# zulu_a7_4.net
KiCad netlist of a schematic drawn in Altium Designer
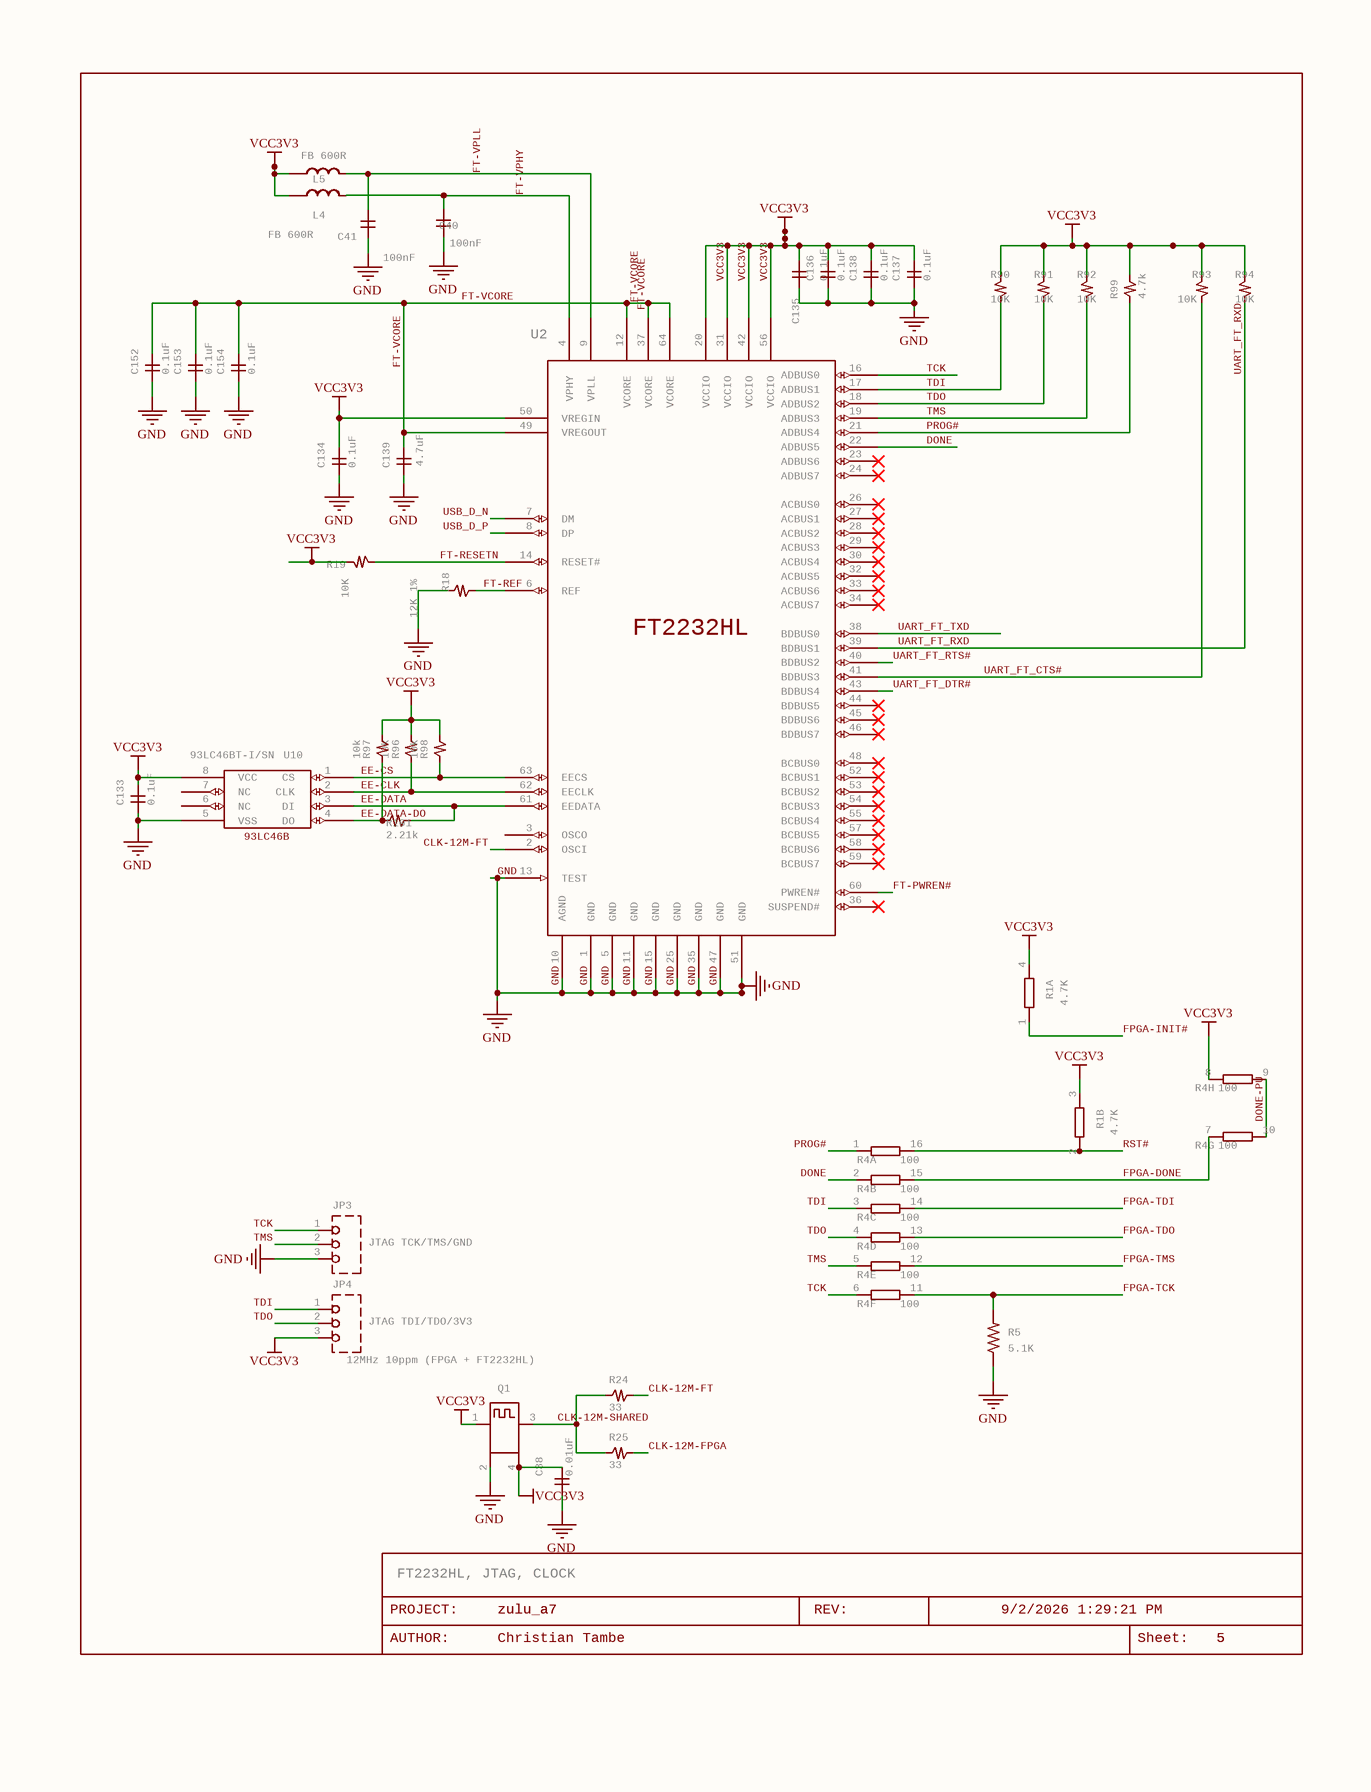
[diagram p0: zulu_a7_4.SchDoc]

(export (version "E")
  (design (tool "Eeschema 10.0.6"))
  (components
    (comp (ref "C38")
      (value "0.01uF")
      (footprint "C0201")
      (description "CAPACITOR, generic non-polarized, horizontal pins")
      (fields (field (name "MANF") "Murata"))
      (libsource (lib "rcl") (part "C-GENERICC0201"))
    )
    (comp (ref "C40")
      (value "100nF")
      (footprint "C0201")
      (description "CAPACITOR, generic non-polarized, horizontal pins")
      (fields (field (name "MANF") "Murata"))
      (libsource (lib "rcl") (part "C-GENERICC0201"))
    )
    (comp (ref "C41")
      (value "100nF")
      (footprint "C0201")
      (description "CAPACITOR, generic non-polarized, horizontal pins")
      (fields (field (name "MANF") "Murata"))
      (libsource (lib "") (part "C-GENERICC0201_2"))
    )
    (comp (ref "C133")
      (value "0.1uF")
      (footprint "C0201")
      (description "CAPACITOR, generic non-polarized, horizontal pins")
      (fields (field (name "MANF") "Murata"))
      (libsource (lib "rcl") (part "C-GENERICC0201"))
    )
    (comp (ref "C134")
      (value "0.1uF")
      (footprint "C0201")
      (description "CAPACITOR, generic non-polarized, horizontal pins")
      (fields (field (name "MANF") "Murata"))
      (libsource (lib "rcl") (part "C-GENERICC0201"))
    )
    (comp (ref "C135")
      (value "0.1uF")
      (footprint "C0201")
      (description "CAPACITOR, generic non-polarized, horizontal pins")
      (fields (field (name "MANF") "Murata"))
      (libsource (lib "rcl") (part "C-GENERICC0201"))
    )
    (comp (ref "C136")
      (value "0.1uF")
      (footprint "C0201")
      (description "CAPACITOR, generic non-polarized, horizontal pins")
      (fields (field (name "MANF") "Murata"))
      (libsource (lib "rcl") (part "C-GENERICC0201"))
    )
    (comp (ref "C137")
      (value "0.1uF")
      (footprint "C0201")
      (description "CAPACITOR, generic non-polarized, horizontal pins")
      (fields (field (name "MANF") "Murata"))
      (libsource (lib "rcl") (part "C-GENERICC0201"))
    )
    (comp (ref "C138")
      (value "0.1uF")
      (footprint "C0201")
      (description "CAPACITOR, generic non-polarized, horizontal pins")
      (fields (field (name "MANF") "Murata"))
      (libsource (lib "rcl") (part "C-GENERICC0201"))
    )
    (comp (ref "C139")
      (value "4.7uF")
      (footprint "C0402")
      (description "CAPACITOR, generic non-polarized, horizontal pins")
      (fields (field (name "MANF") "Taiyo Yuden"))
      (libsource (lib "rcl") (part "C-GENERICC0402"))
    )
    (comp (ref "C152")
      (value "0.1uF")
      (footprint "C0201")
      (description "CAPACITOR, generic non-polarized, horizontal pins")
      (fields (field (name "MANF") "Murata"))
      (libsource (lib "") (part "C-GENERICC0201_1"))
    )
    (comp (ref "C153")
      (value "0.1uF")
      (footprint "C0201")
      (description "CAPACITOR, generic non-polarized, horizontal pins")
      (fields (field (name "MANF") "Murata"))
      (libsource (lib "") (part "C-GENERICC0201_1"))
    )
    (comp (ref "C154")
      (value "0.1uF")
      (footprint "C0201")
      (description "CAPACITOR, generic non-polarized, horizontal pins")
      (fields (field (name "MANF") "Murata"))
      (libsource (lib "") (part "C-GENERICC0201_1"))
    )
    (comp (ref "FRAME4")
      (value "DOCFIELD")
      (description "DOCUMENT FIELD")
      (fields
        (field (name "LAST_DATE_TIME") "9/2/2026 1:29:21 PM")
        (field (name "SHEET") "Sheet:")
        (field (name "SHEET_1") "5")
        (field (name "REV") "REV:")
        (field (name "PROJECT") "PROJECT:")
        (field (name "DRAWING_NAME") "zulu_a7")
        (field (name "AUTHOR") "Christian Tambe")
        (field (name "DRAWING_NAME_1") "zulu_a7")
        (field (name "SHEET_2") "5")
        (field (name "LIBRARYNAME") "ctambe")
      )
      (libsource (lib "ctambe") (part "DOCFIELD"))
    )
    (comp (ref "JP3")
      (value "JTAG TCK/TMS/GND")
      (footprint "1X03-NOSILK")
      (fields (field (name "LIBRARYNAME") "pinhead"))
      (libsource (lib "pinhead") (part "TESTPT-1X3NOSILK"))
    )
    (comp (ref "JP4")
      (value "JTAG TDI/TDO/3V3")
      (footprint "1X03-NOSILK")
      (fields (field (name "LIBRARYNAME") "pinhead"))
      (libsource (lib "pinhead") (part "TESTPT-1X3NOSILK"))
    )
    (comp (ref "L4")
      (value "FB 600R")
      (footprint "IND0603")
      (description "INDUCTOR, generic power inductor")
      (fields (field (name "MANF") "Murata") (field (name "LIBRARYNAME") "ctambe"))
      (libsource (lib "ctambe") (part "INDUCTOR"))
    )
    (comp (ref "L5")
      (value "FB 600R")
      (footprint "IND0603")
      (description "INDUCTOR, generic power inductor")
      (fields (field (name "MANF") "Murata") (field (name "LIBRARYNAME") "ctambe"))
      (libsource (lib "ctambe") (part "INDUCTOR"))
    )
    (comp (ref "Q1")
      (value "12MHz 10ppm (FPGA + FT2232HL)")
      (footprint "32X25")
      (description "Crystal Chip")
      (fields (field (name "MANF") "ECS") (field (name "LIBRARYNAME") "ctambe"))
      (libsource (lib "ctambe") (part "OSC_CHIPASEM1-12MHZ"))
    )
    (comp (ref "R1")
      (value "4.7K")
      (footprint "742C043")
      (description "Resistor 2-pack   Package of two resistors.")
      (fields (field (name "MANF") "CTS") (field (name "LIBRARYNAME") "ctambe"))
      (libsource (lib "") (part "RES2742_1"))
    )
    (comp (ref "R4")
      (value "100")
      (footprint "742C163")
      (description "Resistor 8-pack   Package of eight resistors, six used.")
      (fields (field (name "MANF") "CTS") (field (name "LIBRARYNAME") "ctambe"))
      (libsource (lib "ctambe") (part "RES8742"))
    )
    (comp (ref "R5")
      (value "5.1K")
      (footprint "R0201")
      (description "RESISTOR, American symbol")
      (fields (field (name "MANF") "Yageo"))
      (libsource (lib "rcl") (part "R-US_R0201"))
    )
    (comp (ref "R18")
      (value "12K 1%")
      (footprint "R0402")
      (description "RESISTOR, American symbol, small 2-zigzag variant (sheet 2 only)")
      (fields (field (name "MANF") "Yageo"))
      (libsource (lib "rcl") (part "R-US_SMALLR0402"))
    )
    (comp (ref "R19")
      (value "10K")
      (footprint "R0201")
      (description "RESISTOR, American symbol, small 2-zigzag variant (sheet 2 only)")
      (fields (field (name "MANF") "Yageo"))
      (libsource (lib "rcl") (part "R-US_SMALLR0201"))
    )
    (comp (ref "R24")
      (value "33")
      (footprint "R0201")
      (description "RESISTOR, American symbol, small 2-zigzag variant (sheet 2 only)")
      (fields (field (name "MANF") "Yageo"))
      (libsource (lib "rcl") (part "R-US_SMALLR0201"))
    )
    (comp (ref "R25")
      (value "33")
      (footprint "R0201")
      (description "RESISTOR, American symbol, small 2-zigzag variant (sheet 2 only)")
      (fields (field (name "MANF") "Yageo"))
      (libsource (lib "rcl") (part "R-US_SMALLR0201"))
    )
    (comp (ref "R90")
      (value "10K")
      (footprint "R0201")
      (description "RESISTOR, American symbol, small 2-zigzag variant (sheet 2 only)")
      (fields (field (name "MANF") "Yageo"))
      (libsource (lib "rcl") (part "R-US_SMALLR0201"))
    )
    (comp (ref "R91")
      (value "10K")
      (footprint "R0201")
      (description "RESISTOR, American symbol, small 2-zigzag variant (sheet 2 only)")
      (fields (field (name "MANF") "Yageo"))
      (libsource (lib "rcl") (part "R-US_SMALLR0201"))
    )
    (comp (ref "R92")
      (value "10K")
      (footprint "R0201")
      (description "RESISTOR, American symbol, small 2-zigzag variant (sheet 2 only)")
      (fields (field (name "MANF") "Yageo"))
      (libsource (lib "rcl") (part "R-US_SMALLR0201"))
    )
    (comp (ref "R93")
      (value "10K")
      (footprint "R0201")
      (description "RESISTOR, American symbol, small 2-zigzag variant (sheet 2 only)")
      (fields (field (name "MANF") "Yageo"))
      (libsource (lib "rcl") (part "R-US_SMALLR0201"))
    )
    (comp (ref "R94")
      (value "10K")
      (footprint "R0201")
      (description "RESISTOR, American symbol, small 2-zigzag variant (sheet 2 only)")
      (fields (field (name "MANF") "Yageo"))
      (libsource (lib "rcl") (part "R-US_SMALLR0201"))
    )
    (comp (ref "R96")
      (value "10k")
      (footprint "R0201")
      (description "RESISTOR, American symbol, small 2-zigzag variant (sheet 2 only)")
      (fields (field (name "MANF") "Yageo"))
      (libsource (lib "rcl") (part "R-US_SMALLR0201"))
    )
    (comp (ref "R97")
      (value "10k")
      (footprint "R0201")
      (description "RESISTOR, American symbol, small 2-zigzag variant (sheet 2 only)")
      (fields (field (name "MANF") "Yageo"))
      (libsource (lib "rcl") (part "R-US_SMALLR0201"))
    )
    (comp (ref "R98")
      (value "10k")
      (footprint "R0201")
      (description "RESISTOR, American symbol, small 2-zigzag variant (sheet 2 only)")
      (fields (field (name "MANF") "Yageo"))
      (libsource (lib "rcl") (part "R-US_SMALLR0201"))
    )
    (comp (ref "R99")
      (value "4.7k")
      (footprint "R0201")
      (description "RESISTOR, American symbol, small 2-zigzag variant (sheet 2 only)")
      (fields (field (name "MANF") "Yageo"))
      (libsource (lib "rcl") (part "R-US_SMALLR0201"))
    )
    (comp (ref "R101")
      (value "2.21k")
      (footprint "R0201")
      (description "RESISTOR, American symbol, small 2-zigzag variant (sheet 2 only)")
      (fields (field (name "MANF") "Yageo"))
      (libsource (lib "rcl") (part "R-US_SMALLR0201"))
    )
    (comp (ref "U2")
      (value "FT2232HL USB-UART/JTAG Bridge")
      (footprint "FT2232HL-LQFP64")
      (fields
        (field (name "FT2232HL") "FT2232HL")
        (field (name "MANF") "FTDI")
        (field (name "LIBRARYNAME") "ctambe")
      )
      (libsource (lib "ctambe") (part "FT2232HL-LQFP64"))
    )
    (comp (ref "U10")
      (value "93LC46BT-I/SN")
      (footprint "SPI-8_SOIC_150")
      (fields
        (field (name "93LC46B") "93LC46B")
        (field (name "MANF") "Microchip")
        (field (name "LIBRARYNAME") "ctambe")
      )
      (libsource (lib "ctambe") (part "EEPROM-93LC46B-I/SN"))
    )
  )
  (nets
    (net (code "1") (name "/CLK-12M-FPGA") (class "Default")
      (node (ref "R25") (pin "2") (pinfunction "2_2") (pintype "passive"))
    )
    (net (code "2") (name "/CLK-12M-FT") (class "Default")
      (node (ref "R24") (pin "2") (pinfunction "2_2") (pintype "passive"))
      (node (ref "U2") (pin "2") (pinfunction "OSCI_2") (pintype "bidirectional"))
    )
    (net (code "3") (name "/CLK-12M-SHARED") (class "Default")
      (node (ref "Q1") (pin "3") (pinfunction "3_3") (pintype "passive"))
      (node (ref "R24") (pin "1") (pinfunction "1_1") (pintype "passive"))
      (node (ref "R25") (pin "1") (pinfunction "1_1") (pintype "passive"))
    )
    (net (code "4") (name "/DONE") (class "Default")
      (node (ref "R4") (pin "2") (pinfunction "1_2") (pintype "passive"))
      (node (ref "U2") (pin "22") (pinfunction "ADBUS5_22") (pintype "bidirectional"))
    )
    (net (code "5") (name "/DONE-PU") (class "Default")
      (node (ref "R4") (pin "10") (pinfunction "2_10") (pintype "passive"))
      (node (ref "R4") (pin "9") (pinfunction "2_9") (pintype "passive"))
    )
    (net (code "6") (name "/EE-CLK") (class "Default")
      (node (ref "R96") (pin "1") (pinfunction "1_1") (pintype "passive"))
      (node (ref "U10") (pin "2") (pinfunction "CLK_2") (pintype "bidirectional"))
      (node (ref "U2") (pin "62") (pinfunction "EECLK_62") (pintype "bidirectional"))
    )
    (net (code "7") (name "/EE-CS") (class "Default")
      (node (ref "R98") (pin "1") (pinfunction "1_1") (pintype "passive"))
      (node (ref "U10") (pin "1") (pinfunction "CS_1") (pintype "bidirectional"))
      (node (ref "U2") (pin "63") (pinfunction "EECS_63") (pintype "bidirectional"))
    )
    (net (code "8") (name "/EE-DATA") (class "Default")
      (node (ref "R101") (pin "2") (pinfunction "2_2") (pintype "passive"))
      (node (ref "U10") (pin "3") (pinfunction "DI_3") (pintype "bidirectional"))
      (node (ref "U2") (pin "61") (pinfunction "EEDATA_61") (pintype "bidirectional"))
    )
    (net (code "9") (name "/EE-DATA-DO") (class "Default")
      (node (ref "R101") (pin "1") (pinfunction "1_1") (pintype "passive"))
      (node (ref "R97") (pin "1") (pinfunction "1_1") (pintype "passive"))
      (node (ref "U10") (pin "4") (pinfunction "DO_4") (pintype "bidirectional"))
    )
    (net (code "10") (name "/FPGA-DONE") (class "Default")
      (node (ref "R4") (pin "15") (pinfunction "2_15") (pintype "passive"))
      (node (ref "R4") (pin "7") (pinfunction "1_7") (pintype "passive"))
    )
    (net (code "11") (name "/FPGA-INIT#") (class "Default")
      (node (ref "R1") (pin "1") (pinfunction "1_1") (pintype "passive"))
    )
    (net (code "12") (name "/FPGA-TCK") (class "Default")
      (node (ref "R4") (pin "11") (pinfunction "2_11") (pintype "passive"))
      (node (ref "R5") (pin "2") (pinfunction "2_2") (pintype "passive"))
    )
    (net (code "13") (name "/FPGA-TDI") (class "Default")
      (node (ref "R4") (pin "14") (pinfunction "2_14") (pintype "passive"))
    )
    (net (code "14") (name "/FPGA-TDO") (class "Default")
      (node (ref "R4") (pin "13") (pinfunction "2_13") (pintype "passive"))
    )
    (net (code "15") (name "/FPGA-TMS") (class "Default")
      (node (ref "R4") (pin "12") (pinfunction "2_12") (pintype "passive"))
    )
    (net (code "16") (name "/FT-PWREN#") (class "Default")
      (node (ref "U2") (pin "60") (pinfunction "PWREN#_60") (pintype "bidirectional"))
    )
    (net (code "17") (name "/FT-REF") (class "Default")
      (node (ref "R18") (pin "2") (pinfunction "2_2") (pintype "passive"))
      (node (ref "U2") (pin "6") (pinfunction "REF_6") (pintype "bidirectional"))
    )
    (net (code "18") (name "/FT-RESETN") (class "Default")
      (node (ref "R19") (pin "1") (pinfunction "1_1") (pintype "passive"))
      (node (ref "U2") (pin "14") (pinfunction "RESET#_14") (pintype "bidirectional"))
    )
    (net (code "19") (name "/FT-VCORE") (class "Default")
      (node (ref "C139") (pin "2") (pinfunction "2_2") (pintype "passive"))
      (node (ref "C152") (pin "2") (pinfunction "2_2") (pintype "passive"))
      (node (ref "C153") (pin "2") (pinfunction "2_2") (pintype "passive"))
      (node (ref "C154") (pin "2") (pinfunction "2_2") (pintype "passive"))
      (node (ref "U2") (pin "12") (pinfunction "VCORE_12") (pintype "power_in"))
      (node (ref "U2") (pin "37") (pinfunction "VCORE_37") (pintype "power_in"))
      (node (ref "U2") (pin "49") (pinfunction "VREGOUT_49") (pintype "power_in"))
      (node (ref "U2") (pin "64") (pinfunction "VCORE_64") (pintype "power_in"))
    )
    (net (code "20") (name "/FT-VPHY") (class "Default")
      (node (ref "C40") (pin "2") (pinfunction "2_2") (pintype "passive"))
      (node (ref "L4") (pin "1") (pinfunction "1_1") (pintype "passive"))
      (node (ref "U2") (pin "4") (pinfunction "VPHY_4") (pintype "power_in"))
    )
    (net (code "21") (name "/FT-VPLL") (class "Default")
      (node (ref "C41") (pin "2") (pinfunction "2_2") (pintype "passive"))
      (node (ref "L5") (pin "1") (pinfunction "1_1") (pintype "passive"))
      (node (ref "U2") (pin "9") (pinfunction "VPLL_9") (pintype "power_in"))
    )
    (net (code "22") (name "/PROG#") (class "Default")
      (node (ref "R4") (pin "1") (pinfunction "1_1") (pintype "passive"))
      (node (ref "R99") (pin "1") (pinfunction "1_1") (pintype "passive"))
      (node (ref "U2") (pin "21") (pinfunction "ADBUS4_21") (pintype "bidirectional"))
    )
    (net (code "23") (name "/RST#") (class "Default")
      (node (ref "R1") (pin "2") (pinfunction "1_2") (pintype "passive"))
      (node (ref "R4") (pin "16") (pinfunction "2_16") (pintype "passive"))
    )
    (net (code "24") (name "/TCK") (class "Default")
      (node (ref "JP3") (pin "1") (pinfunction "1_1") (pintype "passive"))
      (node (ref "R4") (pin "6") (pinfunction "1_6") (pintype "passive"))
      (node (ref "U2") (pin "16") (pinfunction "ADBUS0_16") (pintype "bidirectional"))
    )
    (net (code "25") (name "/TDI") (class "Default")
      (node (ref "JP4") (pin "1") (pinfunction "1_1") (pintype "passive"))
      (node (ref "R4") (pin "3") (pinfunction "1_3") (pintype "passive"))
      (node (ref "R90") (pin "1") (pinfunction "1_1") (pintype "passive"))
      (node (ref "U2") (pin "17") (pinfunction "ADBUS1_17") (pintype "bidirectional"))
    )
    (net (code "26") (name "/TDO") (class "Default")
      (node (ref "JP4") (pin "2") (pinfunction "2_2") (pintype "passive"))
      (node (ref "R4") (pin "4") (pinfunction "1_4") (pintype "passive"))
      (node (ref "R91") (pin "1") (pinfunction "1_1") (pintype "passive"))
      (node (ref "U2") (pin "18") (pinfunction "ADBUS2_18") (pintype "bidirectional"))
    )
    (net (code "27") (name "/TMS") (class "Default")
      (node (ref "JP3") (pin "2") (pinfunction "2_2") (pintype "passive"))
      (node (ref "R4") (pin "5") (pinfunction "1_5") (pintype "passive"))
      (node (ref "R92") (pin "1") (pinfunction "1_1") (pintype "passive"))
      (node (ref "U2") (pin "19") (pinfunction "ADBUS3_19") (pintype "bidirectional"))
    )
    (net (code "28") (name "/UART_FT_CTS#") (class "Default")
      (node (ref "R93") (pin "1") (pinfunction "1_1") (pintype "passive"))
      (node (ref "U2") (pin "41") (pinfunction "BDBUS3_41") (pintype "bidirectional"))
    )
    (net (code "29") (name "/UART_FT_DTR#") (class "Default")
      (node (ref "U2") (pin "43") (pinfunction "BDBUS4_43") (pintype "bidirectional"))
    )
    (net (code "30") (name "/UART_FT_RTS#") (class "Default")
      (node (ref "U2") (pin "40") (pinfunction "BDBUS2_40") (pintype "bidirectional"))
    )
    (net (code "31") (name "/UART_FT_RXD") (class "Default")
      (node (ref "R94") (pin "1") (pinfunction "1_1") (pintype "passive"))
      (node (ref "U2") (pin "39") (pinfunction "BDBUS1_39") (pintype "bidirectional"))
    )
    (net (code "32") (name "/UART_FT_TXD") (class "Default")
      (node (ref "U2") (pin "38") (pinfunction "BDBUS0_38") (pintype "bidirectional"))
    )
    (net (code "33") (name "/USB_D_N") (class "Default")
      (node (ref "U2") (pin "7") (pinfunction "DM_7") (pintype "bidirectional"))
    )
    (net (code "34") (name "/USB_D_P") (class "Default")
      (node (ref "U2") (pin "8") (pinfunction "DP_8") (pintype "bidirectional"))
    )
    (net (code "35") (name "GND") (class "Default")
      (node (ref "C133") (pin "1") (pinfunction "1_1") (pintype "passive"))
      (node (ref "C134") (pin "1") (pinfunction "1_1") (pintype "passive"))
      (node (ref "C135") (pin "1") (pinfunction "1_1") (pintype "passive"))
      (node (ref "C136") (pin "1") (pinfunction "1_1") (pintype "passive"))
      (node (ref "C137") (pin "1") (pinfunction "1_1") (pintype "passive"))
      (node (ref "C138") (pin "1") (pinfunction "1_1") (pintype "passive"))
      (node (ref "C139") (pin "1") (pinfunction "1_1") (pintype "passive"))
      (node (ref "C152") (pin "1") (pinfunction "1_1") (pintype "passive"))
      (node (ref "C153") (pin "1") (pinfunction "1_1") (pintype "passive"))
      (node (ref "C154") (pin "1") (pinfunction "1_1") (pintype "passive"))
      (node (ref "C38") (pin "1") (pinfunction "1_1") (pintype "passive"))
      (node (ref "C40") (pin "1") (pinfunction "1_1") (pintype "passive"))
      (node (ref "C41") (pin "1") (pinfunction "1_1") (pintype "passive"))
      (node (ref "JP3") (pin "3") (pinfunction "3_3") (pintype "passive"))
      (node (ref "Q1") (pin "2") (pinfunction "2_2") (pintype "passive"))
      (node (ref "R18") (pin "1") (pinfunction "1_1") (pintype "passive"))
      (node (ref "R5") (pin "1") (pinfunction "1_1") (pintype "passive"))
      (node (ref "U10") (pin "5") (pinfunction "VSS_5") (pintype "power_in"))
      (node (ref "U2") (pin "1") (pinfunction "GND_1") (pintype "power_in"))
      (node (ref "U2") (pin "10") (pinfunction "AGND_10") (pintype "power_in"))
      (node (ref "U2") (pin "11") (pinfunction "GND_11") (pintype "power_in"))
      (node (ref "U2") (pin "13") (pinfunction "TEST_13") (pintype "input"))
      (node (ref "U2") (pin "15") (pinfunction "GND_15") (pintype "power_in"))
      (node (ref "U2") (pin "25") (pinfunction "GND_25") (pintype "power_in"))
      (node (ref "U2") (pin "35") (pinfunction "GND_35") (pintype "power_in"))
      (node (ref "U2") (pin "47") (pinfunction "GND_47") (pintype "power_in"))
      (node (ref "U2") (pin "5") (pinfunction "GND_5") (pintype "power_in"))
      (node (ref "U2") (pin "51") (pinfunction "GND_51") (pintype "power_in"))
    )
    (net (code "36") (name "VCC3V3") (class "Default")
      (node (ref "C133") (pin "2") (pinfunction "2_2") (pintype "passive"))
      (node (ref "C134") (pin "2") (pinfunction "2_2") (pintype "passive"))
      (node (ref "C135") (pin "2") (pinfunction "2_2") (pintype "passive"))
      (node (ref "C136") (pin "2") (pinfunction "2_2") (pintype "passive"))
      (node (ref "C137") (pin "2") (pinfunction "2_2") (pintype "passive"))
      (node (ref "C138") (pin "2") (pinfunction "2_2") (pintype "passive"))
      (node (ref "C38") (pin "2") (pinfunction "2_2") (pintype "passive"))
      (node (ref "JP4") (pin "3") (pinfunction "3_3") (pintype "passive"))
      (node (ref "L4") (pin "2") (pinfunction "2_2") (pintype "passive"))
      (node (ref "L5") (pin "2") (pinfunction "2_2") (pintype "passive"))
      (node (ref "Q1") (pin "1") (pinfunction "1_1") (pintype "passive"))
      (node (ref "Q1") (pin "4") (pinfunction "4_4") (pintype "passive"))
      (node (ref "R1") (pin "3") (pinfunction "2_3") (pintype "passive"))
      (node (ref "R1") (pin "4") (pinfunction "2_4") (pintype "passive"))
      (node (ref "R19") (pin "2") (pinfunction "2_2") (pintype "passive"))
      (node (ref "R4") (pin "8") (pinfunction "1_8") (pintype "passive"))
      (node (ref "R90") (pin "2") (pinfunction "2_2") (pintype "passive"))
      (node (ref "R91") (pin "2") (pinfunction "2_2") (pintype "passive"))
      (node (ref "R92") (pin "2") (pinfunction "2_2") (pintype "passive"))
      (node (ref "R93") (pin "2") (pinfunction "2_2") (pintype "passive"))
      (node (ref "R94") (pin "2") (pinfunction "2_2") (pintype "passive"))
      (node (ref "R96") (pin "2") (pinfunction "2_2") (pintype "passive"))
      (node (ref "R97") (pin "2") (pinfunction "2_2") (pintype "passive"))
      (node (ref "R98") (pin "2") (pinfunction "2_2") (pintype "passive"))
      (node (ref "R99") (pin "2") (pinfunction "2_2") (pintype "passive"))
      (node (ref "U10") (pin "8") (pinfunction "VCC_8") (pintype "power_in"))
      (node (ref "U2") (pin "20") (pinfunction "VCCIO_20") (pintype "power_in"))
      (node (ref "U2") (pin "31") (pinfunction "VCCIO_31") (pintype "power_in"))
      (node (ref "U2") (pin "42") (pinfunction "VCCIO_42") (pintype "power_in"))
      (node (ref "U2") (pin "50") (pinfunction "VREGIN_50") (pintype "power_in"))
      (node (ref "U2") (pin "56") (pinfunction "VCCIO_56") (pintype "power_in"))
    )
    (net (code "37") (name "unconnected-(U2-ACBUS0-Pad26)") (class "Default")
      (node (ref "U2") (pin "26") (pinfunction "ACBUS0_26") (pintype "bidirectional+no_connect"))
    )
    (net (code "38") (name "unconnected-(U2-ACBUS1-Pad27)") (class "Default")
      (node (ref "U2") (pin "27") (pinfunction "ACBUS1_27") (pintype "bidirectional+no_connect"))
    )
    (net (code "39") (name "unconnected-(U2-ACBUS2-Pad28)") (class "Default")
      (node (ref "U2") (pin "28") (pinfunction "ACBUS2_28") (pintype "bidirectional+no_connect"))
    )
    (net (code "40") (name "unconnected-(U2-ACBUS3-Pad29)") (class "Default")
      (node (ref "U2") (pin "29") (pinfunction "ACBUS3_29") (pintype "bidirectional+no_connect"))
    )
    (net (code "41") (name "unconnected-(U2-ACBUS4-Pad30)") (class "Default")
      (node (ref "U2") (pin "30") (pinfunction "ACBUS4_30") (pintype "bidirectional+no_connect"))
    )
    (net (code "42") (name "unconnected-(U2-ACBUS5-Pad32)") (class "Default")
      (node (ref "U2") (pin "32") (pinfunction "ACBUS5_32") (pintype "bidirectional+no_connect"))
    )
    (net (code "43") (name "unconnected-(U2-ACBUS6-Pad33)") (class "Default")
      (node (ref "U2") (pin "33") (pinfunction "ACBUS6_33") (pintype "bidirectional+no_connect"))
    )
    (net (code "44") (name "unconnected-(U2-ACBUS7-Pad34)") (class "Default")
      (node (ref "U2") (pin "34") (pinfunction "ACBUS7_34") (pintype "bidirectional+no_connect"))
    )
    (net (code "45") (name "unconnected-(U2-ADBUS6-Pad23)") (class "Default")
      (node (ref "U2") (pin "23") (pinfunction "ADBUS6_23") (pintype "bidirectional+no_connect"))
    )
    (net (code "46") (name "unconnected-(U2-ADBUS7-Pad24)") (class "Default")
      (node (ref "U2") (pin "24") (pinfunction "ADBUS7_24") (pintype "bidirectional+no_connect"))
    )
    (net (code "47") (name "unconnected-(U2-BCBUS0-Pad48)") (class "Default")
      (node (ref "U2") (pin "48") (pinfunction "BCBUS0_48") (pintype "bidirectional+no_connect"))
    )
    (net (code "48") (name "unconnected-(U2-BCBUS1-Pad52)") (class "Default")
      (node (ref "U2") (pin "52") (pinfunction "BCBUS1_52") (pintype "bidirectional+no_connect"))
    )
    (net (code "49") (name "unconnected-(U2-BCBUS2-Pad53)") (class "Default")
      (node (ref "U2") (pin "53") (pinfunction "BCBUS2_53") (pintype "bidirectional+no_connect"))
    )
    (net (code "50") (name "unconnected-(U2-BCBUS3-Pad54)") (class "Default")
      (node (ref "U2") (pin "54") (pinfunction "BCBUS3_54") (pintype "bidirectional+no_connect"))
    )
    (net (code "51") (name "unconnected-(U2-BCBUS4-Pad55)") (class "Default")
      (node (ref "U2") (pin "55") (pinfunction "BCBUS4_55") (pintype "bidirectional+no_connect"))
    )
    (net (code "52") (name "unconnected-(U2-BCBUS5-Pad57)") (class "Default")
      (node (ref "U2") (pin "57") (pinfunction "BCBUS5_57") (pintype "bidirectional+no_connect"))
    )
    (net (code "53") (name "unconnected-(U2-BCBUS6-Pad58)") (class "Default")
      (node (ref "U2") (pin "58") (pinfunction "BCBUS6_58") (pintype "bidirectional+no_connect"))
    )
    (net (code "54") (name "unconnected-(U2-BCBUS7-Pad59)") (class "Default")
      (node (ref "U2") (pin "59") (pinfunction "BCBUS7_59") (pintype "bidirectional+no_connect"))
    )
    (net (code "55") (name "unconnected-(U2-BDBUS5-Pad44)") (class "Default")
      (node (ref "U2") (pin "44") (pinfunction "BDBUS5_44") (pintype "bidirectional+no_connect"))
    )
    (net (code "56") (name "unconnected-(U2-BDBUS6-Pad45)") (class "Default")
      (node (ref "U2") (pin "45") (pinfunction "BDBUS6_45") (pintype "bidirectional+no_connect"))
    )
    (net (code "57") (name "unconnected-(U2-BDBUS7-Pad46)") (class "Default")
      (node (ref "U2") (pin "46") (pinfunction "BDBUS7_46") (pintype "bidirectional+no_connect"))
    )
    (net (code "58") (name "unconnected-(U2-OSCO-Pad3)") (class "Default")
      (node (ref "U2") (pin "3") (pinfunction "OSCO_3") (pintype "bidirectional"))
    )
    (net (code "59") (name "unconnected-(U2-SUSPEND#-Pad36)") (class "Default")
      (node (ref "U2") (pin "36") (pinfunction "SUSPEND#_36") (pintype "bidirectional+no_connect"))
    )
    (net (code "60") (name "unconnected-(U10-NC-Pad6)") (class "Default")
      (node (ref "U10") (pin "6") (pinfunction "NC_6") (pintype "bidirectional"))
    )
    (net (code "61") (name "unconnected-(U10-NC-Pad7)") (class "Default")
      (node (ref "U10") (pin "7") (pinfunction "NC_7") (pintype "bidirectional"))
    )
  )
)
